# ESP_DRIVE.net
KiCad netlist of a schematic drawn in EAGLE
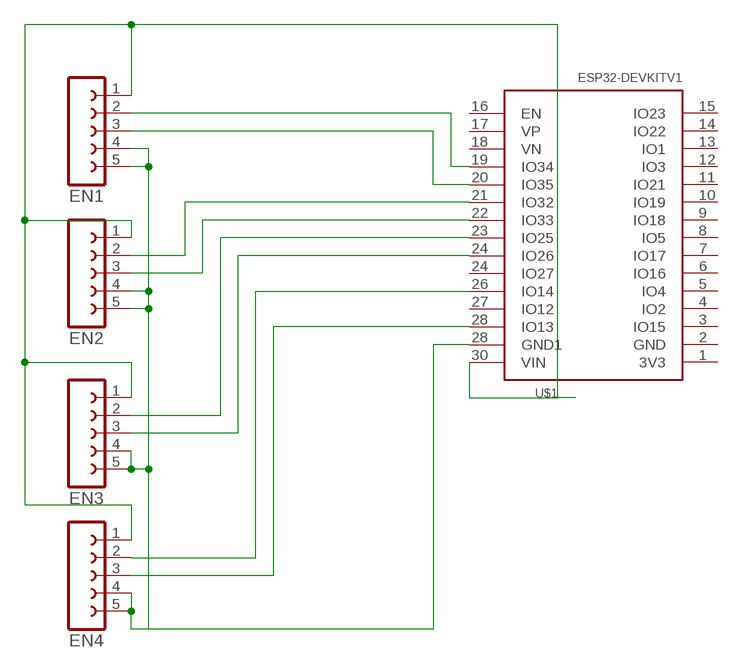
[diagram p0: schematic, sheet 1]

(export (version "E")
  (design (tool "Eeschema 10.0.6"))
  (components
    (comp (ref "EN1")
      (value "FE05-1")
      (footprint "eagle-import:FE05-1")
      (libsource (lib "eagle-import") (part "FE05-1"))
    )
    (comp (ref "EN2")
      (value "FE05-1")
      (footprint "eagle-import:FE05-1")
      (libsource (lib "eagle-import") (part "FE05-1"))
    )
    (comp (ref "EN3")
      (value "FE05-1")
      (footprint "eagle-import:FE05-1")
      (libsource (lib "eagle-import") (part "FE05-1"))
    )
    (comp (ref "EN4")
      (value "FE05-1")
      (footprint "eagle-import:FE05-1")
      (libsource (lib "eagle-import") (part "FE05-1"))
    )
    (comp (ref "U$1")
      (value "ESP32DEVKITV1")
      (footprint "eagle-import:ESP32-DEVKITV1")
      (libsource (lib "eagle-import") (part "ESP32DEVKITV1"))
    )
  )
  (nets
    (net (code "1") (name "Net-(U$1-GND1)") (class "Default")
      (node (ref "EN1") (pin "4") (pinfunction "4_4") (pintype "passive"))
      (node (ref "EN1") (pin "5") (pinfunction "5_5") (pintype "passive"))
      (node (ref "EN2") (pin "4") (pinfunction "4_4") (pintype "passive"))
      (node (ref "EN2") (pin "5") (pinfunction "5_5") (pintype "passive"))
      (node (ref "EN3") (pin "4") (pinfunction "4_4") (pintype "passive"))
      (node (ref "EN3") (pin "5") (pinfunction "5_5") (pintype "passive"))
      (node (ref "EN4") (pin "4") (pinfunction "4_4") (pintype "passive"))
      (node (ref "EN4") (pin "5") (pinfunction "5_5") (pintype "passive"))
      (node (ref "U$1") (pin "28") (pinfunction "GND1_28") (pintype "bidirectional"))
    )
    (net (code "2") (name "Net-(U$1-IO13)") (class "Default")
      (node (ref "EN4") (pin "3") (pinfunction "3_3") (pintype "passive"))
      (node (ref "U$1") (pin "28") (pinfunction "IO13_28") (pintype "bidirectional"))
    )
    (net (code "3") (name "Net-(U$1-IO14)") (class "Default")
      (node (ref "EN4") (pin "2") (pinfunction "2_2") (pintype "passive"))
      (node (ref "U$1") (pin "26") (pinfunction "IO14_26") (pintype "bidirectional"))
    )
    (net (code "4") (name "Net-(U$1-IO25)") (class "Default")
      (node (ref "EN3") (pin "2") (pinfunction "2_2") (pintype "passive"))
      (node (ref "U$1") (pin "23") (pinfunction "IO25_23") (pintype "bidirectional"))
    )
    (net (code "5") (name "Net-(U$1-IO26)") (class "Default")
      (node (ref "EN3") (pin "3") (pinfunction "3_3") (pintype "passive"))
      (node (ref "U$1") (pin "24") (pinfunction "IO26_24") (pintype "bidirectional"))
    )
    (net (code "6") (name "Net-(U$1-IO32)") (class "Default")
      (node (ref "EN2") (pin "2") (pinfunction "2_2") (pintype "passive"))
      (node (ref "U$1") (pin "21") (pinfunction "IO32_21") (pintype "bidirectional"))
    )
    (net (code "7") (name "Net-(U$1-IO33)") (class "Default")
      (node (ref "EN2") (pin "3") (pinfunction "3_3") (pintype "passive"))
      (node (ref "U$1") (pin "22") (pinfunction "IO33_22") (pintype "bidirectional"))
    )
    (net (code "8") (name "Net-(U$1-IO34)") (class "Default")
      (node (ref "EN1") (pin "2") (pinfunction "2_2") (pintype "passive"))
      (node (ref "U$1") (pin "19") (pinfunction "IO34_19") (pintype "bidirectional"))
    )
    (net (code "9") (name "Net-(U$1-IO35)") (class "Default")
      (node (ref "EN1") (pin "3") (pinfunction "3_3") (pintype "passive"))
      (node (ref "U$1") (pin "20") (pinfunction "IO35_20") (pintype "bidirectional"))
    )
    (net (code "10") (name "Net-(U$1-VIN)") (class "Default")
      (node (ref "EN1") (pin "1") (pinfunction "1_1") (pintype "passive"))
      (node (ref "EN2") (pin "1") (pinfunction "1_1") (pintype "passive"))
      (node (ref "EN3") (pin "1") (pinfunction "1_1") (pintype "passive"))
      (node (ref "EN4") (pin "1") (pinfunction "1_1") (pintype "passive"))
      (node (ref "U$1") (pin "30") (pinfunction "VIN_30") (pintype "bidirectional"))
    )
    (net (code "11") (name "unconnected-(U$1-3V3-Pad1)") (class "Default")
      (node (ref "U$1") (pin "1") (pinfunction "3V3_1") (pintype "bidirectional"))
    )
    (net (code "12") (name "unconnected-(U$1-EN-Pad16)") (class "Default")
      (node (ref "U$1") (pin "16") (pinfunction "EN_16") (pintype "bidirectional"))
    )
    (net (code "13") (name "unconnected-(U$1-GND-Pad2)") (class "Default")
      (node (ref "U$1") (pin "2") (pinfunction "GND_2") (pintype "bidirectional"))
    )
    (net (code "14") (name "unconnected-(U$1-IO1-Pad13)") (class "Default")
      (node (ref "U$1") (pin "13") (pinfunction "IO1_13") (pintype "bidirectional"))
    )
    (net (code "15") (name "unconnected-(U$1-IO2-Pad4)") (class "Default")
      (node (ref "U$1") (pin "4") (pinfunction "IO2_4") (pintype "bidirectional"))
    )
    (net (code "16") (name "unconnected-(U$1-IO3-Pad12)") (class "Default")
      (node (ref "U$1") (pin "12") (pinfunction "IO3_12") (pintype "bidirectional"))
    )
    (net (code "17") (name "unconnected-(U$1-IO4-Pad5)") (class "Default")
      (node (ref "U$1") (pin "5") (pinfunction "IO4_5") (pintype "bidirectional"))
    )
    (net (code "18") (name "unconnected-(U$1-IO5-Pad8)") (class "Default")
      (node (ref "U$1") (pin "8") (pinfunction "IO5_8") (pintype "bidirectional"))
    )
    (net (code "19") (name "unconnected-(U$1-IO12-Pad27)") (class "Default")
      (node (ref "U$1") (pin "27") (pinfunction "IO12_27") (pintype "bidirectional"))
    )
    (net (code "20") (name "unconnected-(U$1-IO15-Pad3)") (class "Default")
      (node (ref "U$1") (pin "3") (pinfunction "IO15_3") (pintype "bidirectional"))
    )
    (net (code "21") (name "unconnected-(U$1-IO16-Pad6)") (class "Default")
      (node (ref "U$1") (pin "6") (pinfunction "IO16_6") (pintype "bidirectional"))
    )
    (net (code "22") (name "unconnected-(U$1-IO17-Pad7)") (class "Default")
      (node (ref "U$1") (pin "7") (pinfunction "IO17_7") (pintype "bidirectional"))
    )
    (net (code "23") (name "unconnected-(U$1-IO18-Pad9)") (class "Default")
      (node (ref "U$1") (pin "9") (pinfunction "IO18_9") (pintype "bidirectional"))
    )
    (net (code "24") (name "unconnected-(U$1-IO19-Pad10)") (class "Default")
      (node (ref "U$1") (pin "10") (pinfunction "IO19_10") (pintype "bidirectional"))
    )
    (net (code "25") (name "unconnected-(U$1-IO21-Pad11)") (class "Default")
      (node (ref "U$1") (pin "11") (pinfunction "IO21_11") (pintype "bidirectional"))
    )
    (net (code "26") (name "unconnected-(U$1-IO22-Pad14)") (class "Default")
      (node (ref "U$1") (pin "14") (pinfunction "IO22_14") (pintype "bidirectional"))
    )
    (net (code "27") (name "unconnected-(U$1-IO23-Pad15)") (class "Default")
      (node (ref "U$1") (pin "15") (pinfunction "IO23_15") (pintype "bidirectional"))
    )
    (net (code "28") (name "unconnected-(U$1-IO27-Pad24)") (class "Default")
      (node (ref "U$1") (pin "24") (pinfunction "IO27_24") (pintype "bidirectional"))
    )
    (net (code "29") (name "unconnected-(U$1-VN-Pad18)") (class "Default")
      (node (ref "U$1") (pin "18") (pinfunction "VN_18") (pintype "bidirectional"))
    )
    (net (code "30") (name "unconnected-(U$1-VP-Pad17)") (class "Default")
      (node (ref "U$1") (pin "17") (pinfunction "VP_17") (pintype "bidirectional"))
    )
  )
)
